# practice_2022.net
KiCad netlist of a schematic drawn in EAGLE
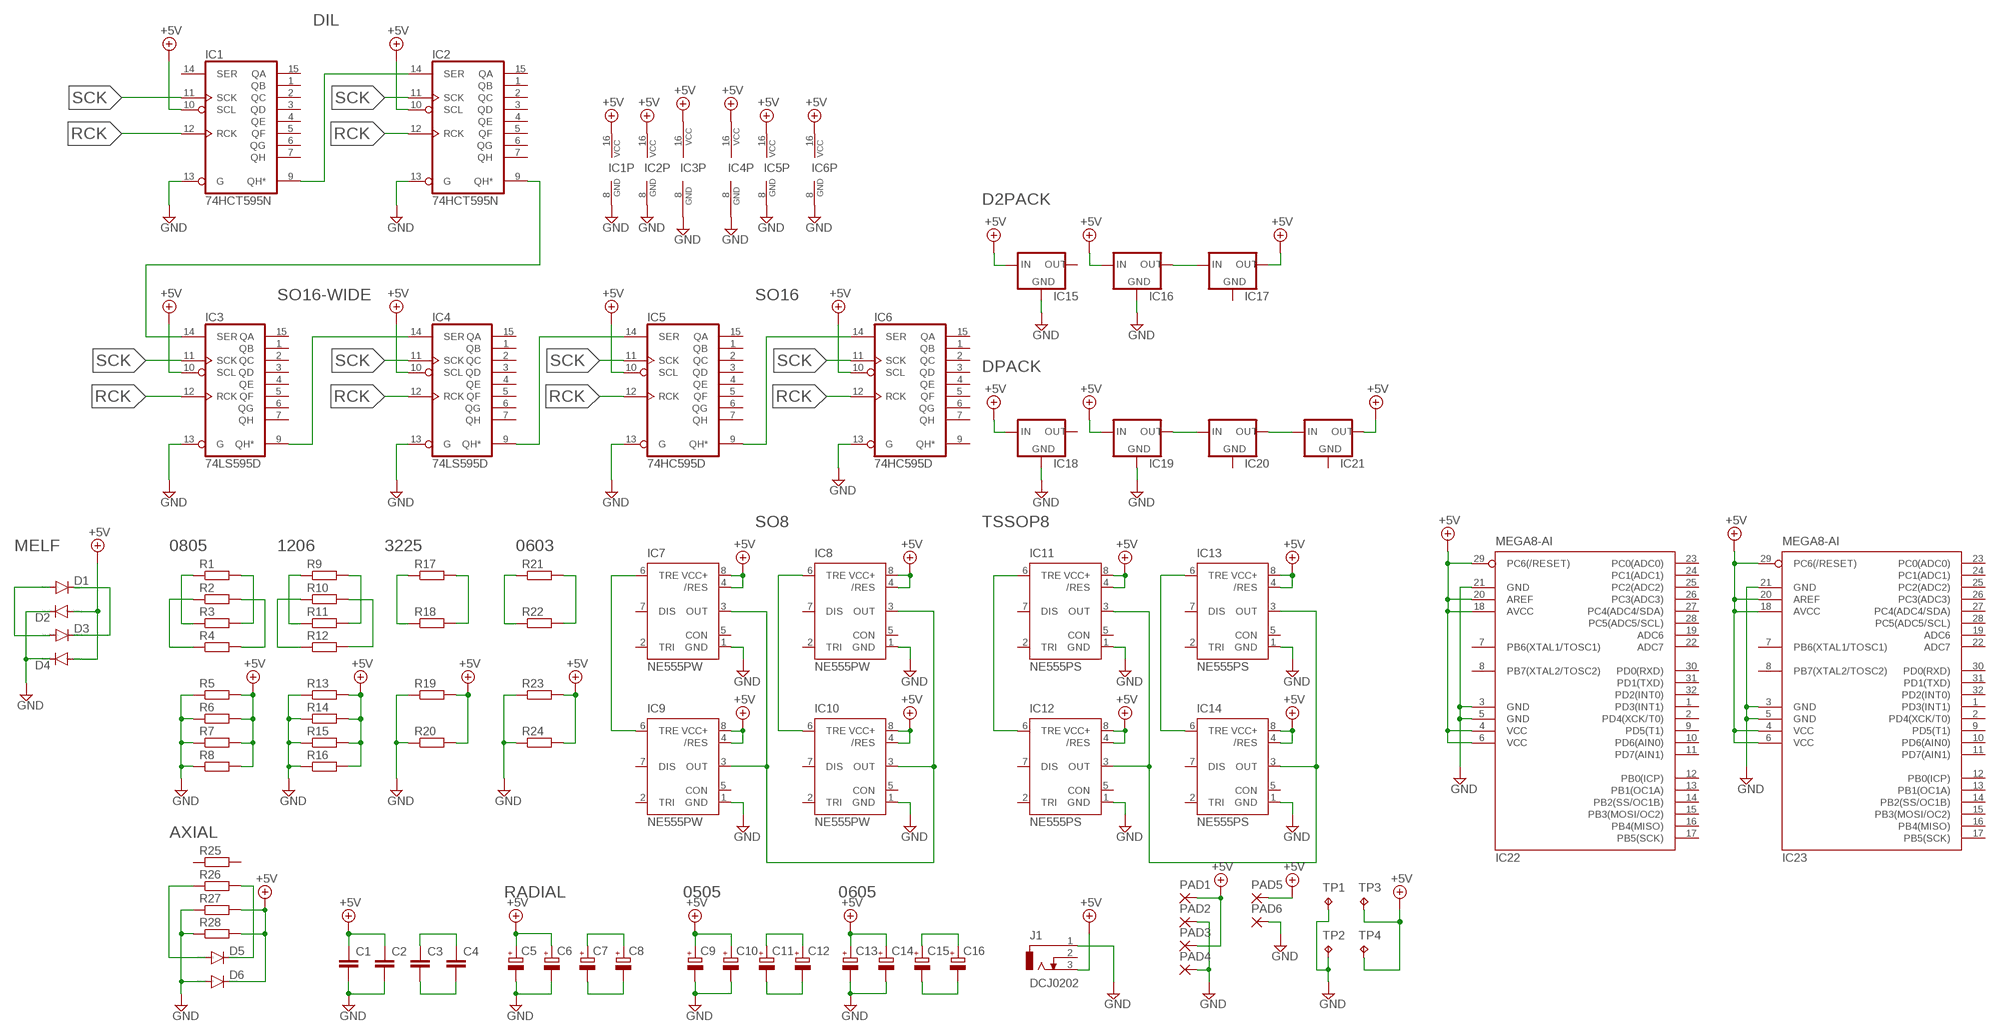
[diagram p0: schematic, sheet 1]

(export (version "E")
  (design (tool "Eeschema 10.0.6"))
  (components
    (comp (ref "C1")
      (value "C-EU050-024X044")
      (footprint "eagle-import:C050-024X044")
      (libsource (lib "eagle-import") (part "C-EU050-024X044"))
    )
    (comp (ref "C2")
      (value "C-EU050-024X044")
      (footprint "eagle-import:C050-024X044")
      (libsource (lib "eagle-import") (part "C-EU050-024X044"))
    )
    (comp (ref "C3")
      (value "C-EU050-024X044")
      (footprint "eagle-import:C050-024X044")
      (libsource (lib "eagle-import") (part "C-EU050-024X044"))
    )
    (comp (ref "C4")
      (value "C-EU050-024X044")
      (footprint "eagle-import:C050-024X044")
      (libsource (lib "eagle-import") (part "C-EU050-024X044"))
    )
    (comp (ref "C5")
      (value "CPOL-EUE5-4")
      (footprint "eagle-import:E5-4")
      (libsource (lib "eagle-import") (part "CPOL-EUE5-4"))
    )
    (comp (ref "C6")
      (value "CPOL-EUE5-4")
      (footprint "eagle-import:E5-4")
      (libsource (lib "eagle-import") (part "CPOL-EUE5-4"))
    )
    (comp (ref "C7")
      (value "CPOL-EUE2,5-6E")
      (footprint "eagle-import:E2,5-6E")
      (libsource (lib "eagle-import") (part "CPOL-EUE2,5-6E"))
    )
    (comp (ref "C8")
      (value "CPOL-EUE2,5-6E")
      (footprint "eagle-import:E2,5-6E")
      (libsource (lib "eagle-import") (part "CPOL-EUE2,5-6E"))
    )
    (comp (ref "C9")
      (value "CPOL-EU153CLV-0505")
      (footprint "eagle-import:153CLV-0505")
      (libsource (lib "eagle-import") (part "CPOL-EU153CLV-0505"))
    )
    (comp (ref "C10")
      (value "CPOL-EU153CLV-0505")
      (footprint "eagle-import:153CLV-0505")
      (libsource (lib "eagle-import") (part "CPOL-EU153CLV-0505"))
    )
    (comp (ref "C11")
      (value "CPOL-EU153CLV-0505")
      (footprint "eagle-import:153CLV-0505")
      (libsource (lib "eagle-import") (part "CPOL-EU153CLV-0505"))
    )
    (comp (ref "C12")
      (value "CPOL-EU153CLV-0505")
      (footprint "eagle-import:153CLV-0505")
      (libsource (lib "eagle-import") (part "CPOL-EU153CLV-0505"))
    )
    (comp (ref "C13")
      (value "CPOL-EU153CLV-0605")
      (footprint "eagle-import:153CLV-0605")
      (libsource (lib "eagle-import") (part "CPOL-EU153CLV-0605"))
    )
    (comp (ref "C14")
      (value "CPOL-EU153CLV-0605")
      (footprint "eagle-import:153CLV-0605")
      (libsource (lib "eagle-import") (part "CPOL-EU153CLV-0605"))
    )
    (comp (ref "C15")
      (value "CPOL-EU153CLV-0605")
      (footprint "eagle-import:153CLV-0605")
      (libsource (lib "eagle-import") (part "CPOL-EU153CLV-0605"))
    )
    (comp (ref "C16")
      (value "CPOL-EU153CLV-0605")
      (footprint "eagle-import:153CLV-0605")
      (libsource (lib "eagle-import") (part "CPOL-EU153CLV-0605"))
    )
    (comp (ref "D1")
      (value "DIODE-MINIMELF")
      (footprint "eagle-import:MINIMELF")
      (libsource (lib "eagle-import") (part "DIODE-MINIMELF"))
    )
    (comp (ref "D2")
      (value "DIODE-MINIMELF")
      (footprint "eagle-import:MINIMELF")
      (libsource (lib "eagle-import") (part "DIODE-MINIMELF"))
    )
    (comp (ref "D3")
      (value "DIODE-MINIMELF")
      (footprint "eagle-import:MINIMELF")
      (libsource (lib "eagle-import") (part "DIODE-MINIMELF"))
    )
    (comp (ref "D4")
      (value "DIODE-MINIMELF")
      (footprint "eagle-import:MINIMELF")
      (libsource (lib "eagle-import") (part "DIODE-MINIMELF"))
    )
    (comp (ref "D5")
      (value "DIODE-DO35-10")
      (footprint "eagle-import:DO35-10")
      (libsource (lib "eagle-import") (part "DIODE-DO35-10"))
    )
    (comp (ref "D6")
      (value "DIODE-DO35-10")
      (footprint "eagle-import:DO35-10")
      (libsource (lib "eagle-import") (part "DIODE-DO35-10"))
    )
    (comp (ref "IC1")
      (value "74HCT595N")
      (footprint "eagle-import:DIL16")
      (libsource (lib "eagle-import") (part "74595NHCT"))
    )
    (comp (ref "IC2")
      (value "74HCT595N")
      (footprint "eagle-import:DIL16")
      (libsource (lib "eagle-import") (part "74595NHCT"))
    )
    (comp (ref "IC3")
      (value "74LS595D")
      (footprint "eagle-import:SO16")
      (libsource (lib "eagle-import") (part "74595DLS"))
    )
    (comp (ref "IC4")
      (value "74LS595D")
      (footprint "eagle-import:SO16")
      (libsource (lib "eagle-import") (part "74595DLS"))
    )
    (comp (ref "IC5")
      (value "74HC595D")
      (footprint "eagle-import:SO16")
      (libsource (lib "eagle-import") (part "74595DHC"))
    )
    (comp (ref "IC6")
      (value "74HC595D")
      (footprint "eagle-import:SO16")
      (libsource (lib "eagle-import") (part "74595DHC"))
    )
    (comp (ref "IC7")
      (value "NE555PW")
      (footprint "eagle-import:TSSOP8")
      (libsource (lib "eagle-import") (part "NE555PW"))
    )
    (comp (ref "IC8")
      (value "NE555PW")
      (footprint "eagle-import:TSSOP8")
      (libsource (lib "eagle-import") (part "NE555PW"))
    )
    (comp (ref "IC9")
      (value "NE555PW")
      (footprint "eagle-import:TSSOP8")
      (libsource (lib "eagle-import") (part "NE555PW"))
    )
    (comp (ref "IC10")
      (value "NE555PW")
      (footprint "eagle-import:TSSOP8")
      (libsource (lib "eagle-import") (part "NE555PW"))
    )
    (comp (ref "IC11")
      (value "NE555PS")
      (footprint "eagle-import:SO08")
      (libsource (lib "eagle-import") (part "NE555PS"))
    )
    (comp (ref "IC12")
      (value "NE555PS")
      (footprint "eagle-import:SO08")
      (libsource (lib "eagle-import") (part "NE555PS"))
    )
    (comp (ref "IC13")
      (value "NE555PS")
      (footprint "eagle-import:SO08")
      (libsource (lib "eagle-import") (part "NE555PS"))
    )
    (comp (ref "IC14")
      (value "NE555PS")
      (footprint "eagle-import:SO08")
      (libsource (lib "eagle-import") (part "NE555PS"))
    )
    (comp (ref "IC15")
      (value "78XX-D2PACK")
      (footprint "eagle-import:D2PACK")
      (libsource (lib "eagle-import") (part "78XX-D2PACK"))
    )
    (comp (ref "IC16")
      (value "78XX-D2PACK")
      (footprint "eagle-import:D2PACK")
      (libsource (lib "eagle-import") (part "78XX-D2PACK"))
    )
    (comp (ref "IC17")
      (value "78XX-D2PACK")
      (footprint "eagle-import:D2PACK")
      (libsource (lib "eagle-import") (part "78XX-D2PACK"))
    )
    (comp (ref "IC18")
      (value "78XX-DPACK")
      (footprint "eagle-import:DPACK")
      (libsource (lib "eagle-import") (part "78XX-DPACK"))
    )
    (comp (ref "IC19")
      (value "78XX-DPACK")
      (footprint "eagle-import:DPACK")
      (libsource (lib "eagle-import") (part "78XX-DPACK"))
    )
    (comp (ref "IC20")
      (value "78XX-DPACK")
      (footprint "eagle-import:DPACK")
      (libsource (lib "eagle-import") (part "78XX-DPACK"))
    )
    (comp (ref "IC21")
      (value "78XX-DPACK")
      (footprint "eagle-import:DPACK")
      (libsource (lib "eagle-import") (part "78XX-DPACK"))
    )
    (comp (ref "IC22")
      (value "MEGA8-AI")
      (footprint "eagle-import:TQFP32-08")
      (fields (field (name "MPN") "ATMEGA8-16AU"))
      (libsource (lib "eagle-import") (part "MEGA8-AI"))
    )
    (comp (ref "IC23")
      (value "MEGA8-AI")
      (footprint "eagle-import:TQFP32-08")
      (fields (field (name "MPN") "ATMEGA8-16AU"))
      (libsource (lib "eagle-import") (part "MEGA8-AI"))
    )
    (comp (ref "J1")
      (value "DCJ0202")
      (footprint "eagle-import:DCJ0202")
      (libsource (lib "eagle-import") (part "DCJ0202"))
    )
    (comp (ref "PAD1")
      (value "SMD2")
      (footprint "eagle-import:SMD1,27-2,54")
      (libsource (lib "eagle-import") (part "SMD2"))
    )
    (comp (ref "PAD2")
      (value "SMD2")
      (footprint "eagle-import:SMD1,27-2,54")
      (libsource (lib "eagle-import") (part "SMD2"))
    )
    (comp (ref "PAD3")
      (value "SMD5")
      (footprint "eagle-import:SMD2,54-5,08")
      (libsource (lib "eagle-import") (part "SMD5"))
    )
    (comp (ref "PAD4")
      (value "SMD5")
      (footprint "eagle-import:SMD2,54-5,08")
      (libsource (lib "eagle-import") (part "SMD5"))
    )
    (comp (ref "PAD5")
      (value "2,54/1,0")
      (footprint "eagle-import:2,54_1,0")
      (libsource (lib "eagle-import") (part "2,54/1,0"))
    )
    (comp (ref "PAD6")
      (value "2,54/1,0")
      (footprint "eagle-import:2,54_1,0")
      (libsource (lib "eagle-import") (part "2,54/1,0"))
    )
    (comp (ref "R1")
      (value "R-EU_R0805")
      (footprint "eagle-import:R0805")
      (libsource (lib "eagle-import") (part "R-EU_R0805"))
    )
    (comp (ref "R2")
      (value "R-EU_R0805")
      (footprint "eagle-import:R0805")
      (libsource (lib "eagle-import") (part "R-EU_R0805"))
    )
    (comp (ref "R3")
      (value "R-EU_R0805")
      (footprint "eagle-import:R0805")
      (libsource (lib "eagle-import") (part "R-EU_R0805"))
    )
    (comp (ref "R4")
      (value "R-EU_R0805")
      (footprint "eagle-import:R0805")
      (libsource (lib "eagle-import") (part "R-EU_R0805"))
    )
    (comp (ref "R5")
      (value "R-EU_R0805")
      (footprint "eagle-import:R0805")
      (libsource (lib "eagle-import") (part "R-EU_R0805"))
    )
    (comp (ref "R6")
      (value "R-EU_R0805")
      (footprint "eagle-import:R0805")
      (libsource (lib "eagle-import") (part "R-EU_R0805"))
    )
    (comp (ref "R7")
      (value "R-EU_R0805")
      (footprint "eagle-import:R0805")
      (libsource (lib "eagle-import") (part "R-EU_R0805"))
    )
    (comp (ref "R8")
      (value "R-EU_R0805")
      (footprint "eagle-import:R0805")
      (libsource (lib "eagle-import") (part "R-EU_R0805"))
    )
    (comp (ref "R9")
      (value "R-EU_R1206")
      (footprint "eagle-import:R1206")
      (libsource (lib "eagle-import") (part "R-EU_R1206"))
    )
    (comp (ref "R10")
      (value "R-EU_R1206")
      (footprint "eagle-import:R1206")
      (libsource (lib "eagle-import") (part "R-EU_R1206"))
    )
    (comp (ref "R11")
      (value "R-EU_R1206")
      (footprint "eagle-import:R1206")
      (libsource (lib "eagle-import") (part "R-EU_R1206"))
    )
    (comp (ref "R12")
      (value "R-EU_R1206")
      (footprint "eagle-import:R1206")
      (libsource (lib "eagle-import") (part "R-EU_R1206"))
    )
    (comp (ref "R13")
      (value "R-EU_R1206")
      (footprint "eagle-import:R1206")
      (libsource (lib "eagle-import") (part "R-EU_R1206"))
    )
    (comp (ref "R14")
      (value "R-EU_R1206")
      (footprint "eagle-import:R1206")
      (libsource (lib "eagle-import") (part "R-EU_R1206"))
    )
    (comp (ref "R15")
      (value "R-EU_R1206")
      (footprint "eagle-import:R1206")
      (libsource (lib "eagle-import") (part "R-EU_R1206"))
    )
    (comp (ref "R16")
      (value "R-EU_R1206")
      (footprint "eagle-import:R1206")
      (libsource (lib "eagle-import") (part "R-EU_R1206"))
    )
    (comp (ref "R17")
      (value "R-EU_R3225")
      (footprint "eagle-import:R3225")
      (libsource (lib "eagle-import") (part "R-EU_R3225"))
    )
    (comp (ref "R18")
      (value "R-EU_R3225")
      (footprint "eagle-import:R3225")
      (libsource (lib "eagle-import") (part "R-EU_R3225"))
    )
    (comp (ref "R19")
      (value "R-EU_R3225")
      (footprint "eagle-import:R3225")
      (libsource (lib "eagle-import") (part "R-EU_R3225"))
    )
    (comp (ref "R20")
      (value "R-EU_R3225")
      (footprint "eagle-import:R3225")
      (libsource (lib "eagle-import") (part "R-EU_R3225"))
    )
    (comp (ref "R21")
      (value "R-EU_R0603")
      (footprint "eagle-import:R0603")
      (libsource (lib "eagle-import") (part "R-EU_R0603"))
    )
    (comp (ref "R22")
      (value "R-EU_R0603")
      (footprint "eagle-import:R0603")
      (libsource (lib "eagle-import") (part "R-EU_R0603"))
    )
    (comp (ref "R23")
      (value "R-EU_R0603")
      (footprint "eagle-import:R0603")
      (libsource (lib "eagle-import") (part "R-EU_R0603"))
    )
    (comp (ref "R24")
      (value "R-EU_R0603")
      (footprint "eagle-import:R0603")
      (libsource (lib "eagle-import") (part "R-EU_R0603"))
    )
    (comp (ref "R25")
      (value "R-EU_0207/12")
      (footprint "eagle-import:0207_12")
      (libsource (lib "eagle-import") (part "R-EU_0207/12"))
    )
    (comp (ref "R26")
      (value "R-EU_0207/12")
      (footprint "eagle-import:0207_12")
      (libsource (lib "eagle-import") (part "R-EU_0207/12"))
    )
    (comp (ref "R27")
      (value "R-EU_0207/12")
      (footprint "eagle-import:0207_12")
      (libsource (lib "eagle-import") (part "R-EU_0207/12"))
    )
    (comp (ref "R28")
      (value "R-EU_0207/12")
      (footprint "eagle-import:0207_12")
      (libsource (lib "eagle-import") (part "R-EU_0207/12"))
    )
    (comp (ref "TP1")
      (value "TPTP20SQ")
      (footprint "eagle-import:TP20SQ")
      (libsource (lib "eagle-import") (part "TPTP20SQ"))
    )
    (comp (ref "TP2")
      (value "TPTP20SQ")
      (footprint "eagle-import:TP20SQ")
      (libsource (lib "eagle-import") (part "TPTP20SQ"))
    )
    (comp (ref "TP3")
      (value "TPTP06R")
      (footprint "eagle-import:TP06R")
      (libsource (lib "eagle-import") (part "TPTP06R"))
    )
    (comp (ref "TP4")
      (value "TPTP06R")
      (footprint "eagle-import:TP06R")
      (libsource (lib "eagle-import") (part "TPTP06R"))
    )
  )
  (nets
    (net (code "1") (name "+5V") (class "Default")
      (node (ref "C1") (pin "1") (pinfunction "1_1") (pintype "passive"))
      (node (ref "C10") (pin "+") (pinfunction "+_+") (pintype "passive"))
      (node (ref "C13") (pin "+") (pinfunction "+_+") (pintype "passive"))
      (node (ref "C14") (pin "+") (pinfunction "+_+") (pintype "passive"))
      (node (ref "C2") (pin "1") (pinfunction "1_1") (pintype "passive"))
      (node (ref "C5") (pin "+") (pinfunction "+_+") (pintype "passive"))
      (node (ref "C6") (pin "+") (pinfunction "+_+") (pintype "passive"))
      (node (ref "C9") (pin "+") (pinfunction "+_+") (pintype "passive"))
      (node (ref "D2") (pin "A") (pinfunction "A_A") (pintype "passive"))
      (node (ref "D4") (pin "A") (pinfunction "A_A") (pintype "passive"))
      (node (ref "D6") (pin "C") (pinfunction "C_C") (pintype "passive"))
      (node (ref "IC1") (pin "10") (pinfunction "SCL_10") (pintype "input"))
      (node (ref "IC1") (pin "16") (pinfunction "VCC_16") (pintype "power_in"))
      (node (ref "IC10") (pin "4") (pinfunction "/RES_4") (pintype "input"))
      (node (ref "IC10") (pin "8") (pinfunction "VCC+_8") (pintype "power_in"))
      (node (ref "IC11") (pin "4") (pinfunction "/RES_4") (pintype "input"))
      (node (ref "IC11") (pin "8") (pinfunction "VCC+_8") (pintype "power_in"))
      (node (ref "IC12") (pin "4") (pinfunction "/RES_4") (pintype "input"))
      (node (ref "IC12") (pin "8") (pinfunction "VCC+_8") (pintype "power_in"))
      (node (ref "IC13") (pin "4") (pinfunction "/RES_4") (pintype "input"))
      (node (ref "IC13") (pin "8") (pinfunction "VCC+_8") (pintype "power_in"))
      (node (ref "IC14") (pin "4") (pinfunction "/RES_4") (pintype "input"))
      (node (ref "IC14") (pin "8") (pinfunction "VCC+_8") (pintype "power_in"))
      (node (ref "IC15") (pin "1") (pinfunction "IN_1") (pintype "input"))
      (node (ref "IC16") (pin "1") (pinfunction "IN_1") (pintype "input"))
      (node (ref "IC17") (pin "3") (pinfunction "OUT_3") (pintype "passive"))
      (node (ref "IC18") (pin "1") (pinfunction "IN_1") (pintype "input"))
      (node (ref "IC19") (pin "1") (pinfunction "IN_1") (pintype "input"))
      (node (ref "IC2") (pin "10") (pinfunction "SCL_10") (pintype "input"))
      (node (ref "IC2") (pin "16") (pinfunction "VCC_16") (pintype "power_in"))
      (node (ref "IC21") (pin "3") (pinfunction "OUT_3") (pintype "passive"))
      (node (ref "IC22") (pin "18") (pinfunction "AVCC_18") (pintype "power_in"))
      (node (ref "IC22") (pin "20") (pinfunction "AREF_20") (pintype "passive"))
      (node (ref "IC22") (pin "29") (pinfunction "PC6(/RESET)_29") (pintype "bidirectional"))
      (node (ref "IC22") (pin "4") (pinfunction "VCC_4") (pintype "power_in"))
      (node (ref "IC22") (pin "6") (pinfunction "VCC_6") (pintype "power_in"))
      (node (ref "IC23") (pin "18") (pinfunction "AVCC_18") (pintype "power_in"))
      (node (ref "IC23") (pin "20") (pinfunction "AREF_20") (pintype "passive"))
      (node (ref "IC23") (pin "29") (pinfunction "PC6(/RESET)_29") (pintype "bidirectional"))
      (node (ref "IC23") (pin "4") (pinfunction "VCC_4") (pintype "power_in"))
      (node (ref "IC23") (pin "6") (pinfunction "VCC_6") (pintype "power_in"))
      (node (ref "IC3") (pin "10") (pinfunction "SCL_10") (pintype "input"))
      (node (ref "IC3") (pin "16") (pinfunction "VCC_16") (pintype "power_in"))
      (node (ref "IC4") (pin "10") (pinfunction "SCL_10") (pintype "input"))
      (node (ref "IC4") (pin "16") (pinfunction "VCC_16") (pintype "power_in"))
      (node (ref "IC5") (pin "10") (pinfunction "SCL_10") (pintype "input"))
      (node (ref "IC5") (pin "16") (pinfunction "VCC_16") (pintype "power_in"))
      (node (ref "IC6") (pin "10") (pinfunction "SCL_10") (pintype "input"))
      (node (ref "IC6") (pin "16") (pinfunction "VCC_16") (pintype "power_in"))
      (node (ref "IC7") (pin "4") (pinfunction "/RES_4") (pintype "input"))
      (node (ref "IC7") (pin "8") (pinfunction "VCC+_8") (pintype "power_in"))
      (node (ref "IC8") (pin "4") (pinfunction "/RES_4") (pintype "input"))
      (node (ref "IC8") (pin "8") (pinfunction "VCC+_8") (pintype "power_in"))
      (node (ref "IC9") (pin "4") (pinfunction "/RES_4") (pintype "input"))
      (node (ref "IC9") (pin "8") (pinfunction "VCC+_8") (pintype "power_in"))
      (node (ref "J1") (pin "3") (pinfunction "3_3") (pintype "passive"))
      (node (ref "PAD1") (pin "1") (pinfunction "P_1") (pintype "passive"))
      (node (ref "PAD3") (pin "1") (pinfunction "P_1") (pintype "passive"))
      (node (ref "PAD5") (pin "1") (pinfunction "P_1") (pintype "passive"))
      (node (ref "R13") (pin "2") (pinfunction "2_2") (pintype "passive"))
      (node (ref "R14") (pin "2") (pinfunction "2_2") (pintype "passive"))
      (node (ref "R15") (pin "2") (pinfunction "2_2") (pintype "passive"))
      (node (ref "R16") (pin "2") (pinfunction "2_2") (pintype "passive"))
      (node (ref "R19") (pin "2") (pinfunction "2_2") (pintype "passive"))
      (node (ref "R20") (pin "2") (pinfunction "2_2") (pintype "passive"))
      (node (ref "R23") (pin "2") (pinfunction "2_2") (pintype "passive"))
      (node (ref "R24") (pin "2") (pinfunction "2_2") (pintype "passive"))
      (node (ref "R27") (pin "2") (pinfunction "2_2") (pintype "passive"))
      (node (ref "R28") (pin "2") (pinfunction "2_2") (pintype "passive"))
      (node (ref "R5") (pin "2") (pinfunction "2_2") (pintype "passive"))
      (node (ref "R6") (pin "2") (pinfunction "2_2") (pintype "passive"))
      (node (ref "R7") (pin "2") (pinfunction "2_2") (pintype "passive"))
      (node (ref "R8") (pin "2") (pinfunction "2_2") (pintype "passive"))
      (node (ref "TP3") (pin "TP") (pinfunction "TP_TP") (pintype "input"))
      (node (ref "TP4") (pin "TP") (pinfunction "TP_TP") (pintype "input"))
    )
    (net (code "2") (name "GND") (class "Default")
      (node (ref "C1") (pin "2") (pinfunction "2_2") (pintype "passive"))
      (node (ref "C10") (pin "-") (pinfunction "-_-") (pintype "passive"))
      (node (ref "C13") (pin "-") (pinfunction "-_-") (pintype "passive"))
      (node (ref "C14") (pin "-") (pinfunction "-_-") (pintype "passive"))
      (node (ref "C2") (pin "2") (pinfunction "2_2") (pintype "passive"))
      (node (ref "C5") (pin "-") (pinfunction "-_-") (pintype "passive"))
      (node (ref "C6") (pin "-") (pinfunction "-_-") (pintype "passive"))
      (node (ref "C9") (pin "-") (pinfunction "-_-") (pintype "passive"))
      (node (ref "D2") (pin "C") (pinfunction "C_C") (pintype "passive"))
      (node (ref "D4") (pin "C") (pinfunction "C_C") (pintype "passive"))
      (node (ref "D6") (pin "A") (pinfunction "A_A") (pintype "passive"))
      (node (ref "IC1") (pin "13") (pinfunction "G_13") (pintype "input"))
      (node (ref "IC1") (pin "8") (pinfunction "GND_8") (pintype "power_in"))
      (node (ref "IC10") (pin "1") (pinfunction "GND_1") (pintype "power_in"))
      (node (ref "IC11") (pin "1") (pinfunction "GND_1") (pintype "power_in"))
      (node (ref "IC12") (pin "1") (pinfunction "GND_1") (pintype "power_in"))
      (node (ref "IC13") (pin "1") (pinfunction "GND_1") (pintype "power_in"))
      (node (ref "IC14") (pin "1") (pinfunction "GND_1") (pintype "power_in"))
      (node (ref "IC15") (pin "2") (pinfunction "GND_2") (pintype "input"))
      (node (ref "IC16") (pin "2") (pinfunction "GND_2") (pintype "input"))
      (node (ref "IC18") (pin "4") (pinfunction "GND_4") (pintype "input"))
      (node (ref "IC19") (pin "4") (pinfunction "GND_4") (pintype "input"))
      (node (ref "IC2") (pin "13") (pinfunction "G_13") (pintype "input"))
      (node (ref "IC2") (pin "8") (pinfunction "GND_8") (pintype "power_in"))
      (node (ref "IC22") (pin "21") (pinfunction "GND_21") (pintype "power_in"))
      (node (ref "IC22") (pin "3") (pinfunction "GND_3") (pintype "power_in"))
      (node (ref "IC22") (pin "5") (pinfunction "GND_5") (pintype "power_in"))
      (node (ref "IC23") (pin "21") (pinfunction "GND_21") (pintype "power_in"))
      (node (ref "IC23") (pin "3") (pinfunction "GND_3") (pintype "power_in"))
      (node (ref "IC23") (pin "5") (pinfunction "GND_5") (pintype "power_in"))
      (node (ref "IC3") (pin "13") (pinfunction "G_13") (pintype "input"))
      (node (ref "IC3") (pin "8") (pinfunction "GND_8") (pintype "power_in"))
      (node (ref "IC4") (pin "13") (pinfunction "G_13") (pintype "input"))
      (node (ref "IC4") (pin "8") (pinfunction "GND_8") (pintype "power_in"))
      (node (ref "IC5") (pin "13") (pinfunction "G_13") (pintype "input"))
      (node (ref "IC5") (pin "8") (pinfunction "GND_8") (pintype "power_in"))
      (node (ref "IC6") (pin "13") (pinfunction "G_13") (pintype "input"))
      (node (ref "IC6") (pin "8") (pinfunction "GND_8") (pintype "power_in"))
      (node (ref "IC7") (pin "1") (pinfunction "GND_1") (pintype "power_in"))
      (node (ref "IC8") (pin "1") (pinfunction "GND_1") (pintype "power_in"))
      (node (ref "IC9") (pin "1") (pinfunction "GND_1") (pintype "power_in"))
      (node (ref "J1") (pin "1") (pinfunction "1_1") (pintype "passive"))
      (node (ref "PAD2") (pin "1") (pinfunction "P_1") (pintype "passive"))
      (node (ref "PAD4") (pin "1") (pinfunction "P_1") (pintype "passive"))
      (node (ref "PAD6") (pin "1") (pinfunction "P_1") (pintype "passive"))
      (node (ref "R13") (pin "1") (pinfunction "1_1") (pintype "passive"))
      (node (ref "R14") (pin "1") (pinfunction "1_1") (pintype "passive"))
      (node (ref "R15") (pin "1") (pinfunction "1_1") (pintype "passive"))
      (node (ref "R16") (pin "1") (pinfunction "1_1") (pintype "passive"))
      (node (ref "R19") (pin "1") (pinfunction "1_1") (pintype "passive"))
      (node (ref "R20") (pin "1") (pinfunction "1_1") (pintype "passive"))
      (node (ref "R23") (pin "1") (pinfunction "1_1") (pintype "passive"))
      (node (ref "R24") (pin "1") (pinfunction "1_1") (pintype "passive"))
      (node (ref "R27") (pin "1") (pinfunction "1_1") (pintype "passive"))
      (node (ref "R28") (pin "1") (pinfunction "1_1") (pintype "passive"))
      (node (ref "R5") (pin "1") (pinfunction "1_1") (pintype "passive"))
      (node (ref "R6") (pin "1") (pinfunction "1_1") (pintype "passive"))
      (node (ref "R7") (pin "1") (pinfunction "1_1") (pintype "passive"))
      (node (ref "R8") (pin "1") (pinfunction "1_1") (pintype "passive"))
      (node (ref "TP1") (pin "TP") (pinfunction "TP_TP") (pintype "input"))
      (node (ref "TP2") (pin "TP") (pinfunction "TP_TP") (pintype "input"))
    )
    (net (code "3") (name "Net-(C3-Pad1)") (class "Default")
      (node (ref "C3") (pin "1") (pinfunction "1_1") (pintype "passive"))
      (node (ref "C4") (pin "1") (pinfunction "1_1") (pintype "passive"))
    )
    (net (code "4") (name "Net-(C3-Pad2)") (class "Default")
      (node (ref "C3") (pin "2") (pinfunction "2_2") (pintype "passive"))
      (node (ref "C4") (pin "2") (pinfunction "2_2") (pintype "passive"))
    )
    (net (code "5") (name "Net-(C7-Pad+)") (class "Default")
      (node (ref "C7") (pin "+") (pinfunction "+_+") (pintype "passive"))
      (node (ref "C8") (pin "+") (pinfunction "+_+") (pintype "passive"))
    )
    (net (code "6") (name "Net-(C7-Pad-)") (class "Default")
      (node (ref "C7") (pin "-") (pinfunction "-_-") (pintype "passive"))
      (node (ref "C8") (pin "-") (pinfunction "-_-") (pintype "passive"))
    )
    (net (code "7") (name "Net-(C11-Pad+)") (class "Default")
      (node (ref "C11") (pin "+") (pinfunction "+_+") (pintype "passive"))
      (node (ref "C12") (pin "+") (pinfunction "+_+") (pintype "passive"))
    )
    (net (code "8") (name "Net-(C11-Pad-)") (class "Default")
      (node (ref "C11") (pin "-") (pinfunction "-_-") (pintype "passive"))
      (node (ref "C12") (pin "-") (pinfunction "-_-") (pintype "passive"))
    )
    (net (code "9") (name "Net-(C15-Pad+)") (class "Default")
      (node (ref "C15") (pin "+") (pinfunction "+_+") (pintype "passive"))
      (node (ref "C16") (pin "+") (pinfunction "+_+") (pintype "passive"))
    )
    (net (code "10") (name "Net-(C15-Pad-)") (class "Default")
      (node (ref "C15") (pin "-") (pinfunction "-_-") (pintype "passive"))
      (node (ref "C16") (pin "-") (pinfunction "-_-") (pintype "passive"))
    )
    (net (code "11") (name "Net-(D1-PadA)") (class "Default")
      (node (ref "D1") (pin "A") (pinfunction "A_A") (pintype "passive"))
      (node (ref "D3") (pin "A") (pinfunction "A_A") (pintype "passive"))
    )
    (net (code "12") (name "Net-(D1-PadC)") (class "Default")
      (node (ref "D1") (pin "C") (pinfunction "C_C") (pintype "passive"))
      (node (ref "D3") (pin "C") (pinfunction "C_C") (pintype "passive"))
    )
    (net (code "13") (name "Net-(D5-PadA)") (class "Default")
      (node (ref "D5") (pin "A") (pinfunction "A_A") (pintype "passive"))
      (node (ref "R26") (pin "1") (pinfunction "1_1") (pintype "passive"))
    )
    (net (code "14") (name "Net-(D5-PadC)") (class "Default")
      (node (ref "D5") (pin "C") (pinfunction "C_C") (pintype "passive"))
      (node (ref "R26") (pin "2") (pinfunction "2_2") (pintype "passive"))
    )
    (net (code "15") (name "Net-(IC1A-QH*)") (class "Default")
      (node (ref "IC1") (pin "9") (pinfunction "QH*_9") (pintype "tri_state"))
      (node (ref "IC2") (pin "14") (pinfunction "SER_14") (pintype "input"))
    )
    (net (code "16") (name "Net-(IC2A-QH*)") (class "Default")
      (node (ref "IC2") (pin "9") (pinfunction "QH*_9") (pintype "tri_state"))
      (node (ref "IC3") (pin "14") (pinfunction "SER_14") (pintype "input"))
    )
    (net (code "17") (name "Net-(IC3A-QH*)") (class "Default")
      (node (ref "IC3") (pin "9") (pinfunction "QH*_9") (pintype "tri_state"))
      (node (ref "IC4") (pin "14") (pinfunction "SER_14") (pintype "input"))
    )
    (net (code "18") (name "Net-(IC4A-QH*)") (class "Default")
      (node (ref "IC4") (pin "9") (pinfunction "QH*_9") (pintype "tri_state"))
      (node (ref "IC5") (pin "14") (pinfunction "SER_14") (pintype "input"))
    )
    (net (code "19") (name "Net-(IC5A-QH*)") (class "Default")
      (node (ref "IC5") (pin "9") (pinfunction "QH*_9") (pintype "tri_state"))
      (node (ref "IC6") (pin "14") (pinfunction "SER_14") (pintype "input"))
    )
    (net (code "20") (name "Net-(IC7-TRE)") (class "Default")
      (node (ref "IC7") (pin "6") (pinfunction "TRE_6") (pintype "input"))
      (node (ref "IC9") (pin "6") (pinfunction "TRE_6") (pintype "input"))
    )
    (net (code "21") (name "Net-(IC10-OUT)") (class "Default")
      (node (ref "IC10") (pin "3") (pinfunction "OUT_3") (pintype "output"))
      (node (ref "IC7") (pin "3") (pinfunction "OUT_3") (pintype "output"))
      (node (ref "IC8") (pin "3") (pinfunction "OUT_3") (pintype "output"))
      (node (ref "IC9") (pin "3") (pinfunction "OUT_3") (pintype "output"))
    )
    (net (code "22") (name "Net-(IC10-TRE)") (class "Default")
      (node (ref "IC10") (pin "6") (pinfunction "TRE_6") (pintype "input"))
      (node (ref "IC8") (pin "6") (pinfunction "TRE_6") (pintype "input"))
    )
    (net (code "23") (name "Net-(IC11-OUT)") (class "Default")
      (node (ref "IC11") (pin "3") (pinfunction "OUT_3") (pintype "output"))
      (node (ref "IC12") (pin "3") (pinfunction "OUT_3") (pintype "output"))
      (node (ref "IC13") (pin "3") (pinfunction "OUT_3") (pintype "output"))
      (node (ref "IC14") (pin "3") (pinfunction "OUT_3") (pintype "output"))
    )
    (net (code "24") (name "Net-(IC11-TRE)") (class "Default")
      (node (ref "IC11") (pin "6") (pinfunction "TRE_6") (pintype "input"))
      (node (ref "IC12") (pin "6") (pinfunction "TRE_6") (pintype "input"))
    )
    (net (code "25") (name "Net-(IC13-TRE)") (class "Default")
      (node (ref "IC13") (pin "6") (pinfunction "TRE_6") (pintype "input"))
      (node (ref "IC14") (pin "6") (pinfunction "TRE_6") (pintype "input"))
    )
    (net (code "26") (name "Net-(IC16-OUT)") (class "Default")
      (node (ref "IC16") (pin "3") (pinfunction "OUT_3") (pintype "passive"))
      (node (ref "IC17") (pin "1") (pinfunction "IN_1") (pintype "input"))
    )
    (net (code "27") (name "Net-(IC19-OUT)") (class "Default")
      (node (ref "IC19") (pin "3") (pinfunction "OUT_3") (pintype "passive"))
      (node (ref "IC20") (pin "1") (pinfunction "IN_1") (pintype "input"))
    )
    (net (code "28") (name "Net-(IC20-OUT)") (class "Default")
      (node (ref "IC20") (pin "3") (pinfunction "OUT_3") (pintype "passive"))
      (node (ref "IC21") (pin "1") (pinfunction "IN_1") (pintype "input"))
    )
    (net (code "29") (name "Net-(R1-Pad1)") (class "Default")
      (node (ref "R1") (pin "1") (pinfunction "1_1") (pintype "passive"))
      (node (ref "R3") (pin "1") (pinfunction "1_1") (pintype "passive"))
    )
    (net (code "30") (name "Net-(R1-Pad2)") (class "Default")
      (node (ref "R1") (pin "2") (pinfunction "2_2") (pintype "passive"))
      (node (ref "R3") (pin "2") (pinfunction "2_2") (pintype "passive"))
    )
    (net (code "31") (name "Net-(R2-Pad1)") (class "Default")
      (node (ref "R2") (pin "1") (pinfunction "1_1") (pintype "passive"))
      (node (ref "R4") (pin "1") (pinfunction "1_1") (pintype "passive"))
    )
    (net (code "32") (name "Net-(R2-Pad2)") (class "Default")
      (node (ref "R2") (pin "2") (pinfunction "2_2") (pintype "passive"))
      (node (ref "R4") (pin "2") (pinfunction "2_2") (pintype "passive"))
    )
    (net (code "33") (name "Net-(R10-Pad1)") (class "Default")
      (node (ref "R10") (pin "1") (pinfunction "1_1") (pintype "passive"))
      (node (ref "R12") (pin "1") (pinfunction "1_1") (pintype "passive"))
    )
    (net (code "34") (name "Net-(R10-Pad2)") (class "Default")
      (node (ref "R10") (pin "2") (pinfunction "2_2") (pintype "passive"))
      (node (ref "R12") (pin "2") (pinfunction "2_2") (pintype "passive"))
    )
    (net (code "35") (name "Net-(R11-Pad1)") (class "Default")
      (node (ref "R11") (pin "1") (pinfunction "1_1") (pintype "passive"))
      (node (ref "R9") (pin "1") (pinfunction "1_1") (pintype "passive"))
    )
    (net (code "36") (name "Net-(R11-Pad2)") (class "Default")
      (node (ref "R11") (pin "2") (pinfunction "2_2") (pintype "passive"))
      (node (ref "R9") (pin "2") (pinfunction "2_2") (pintype "passive"))
    )
    (net (code "37") (name "Net-(R17-Pad1)") (class "Default")
      (node (ref "R17") (pin "1") (pinfunction "1_1") (pintype "passive"))
      (node (ref "R18") (pin "1") (pinfunction "1_1") (pintype "passive"))
    )
    (net (code "38") (name "Net-(R17-Pad2)") (class "Default")
      (node (ref "R17") (pin "2") (pinfunction "2_2") (pintype "passive"))
      (node (ref "R18") (pin "2") (pinfunction "2_2") (pintype "passive"))
    )
    (net (code "39") (name "Net-(R21-Pad1)") (class "Default")
      (node (ref "R21") (pin "1") (pinfunction "1_1") (pintype "passive"))
      (node (ref "R22") (pin "1") (pinfunction "1_1") (pintype "passive"))
    )
    (net (code "40") (name "Net-(R21-Pad2)") (class "Default")
      (node (ref "R21") (pin "2") (pinfunction "2_2") (pintype "passive"))
      (node (ref "R22") (pin "2") (pinfunction "2_2") (pintype "passive"))
    )
    (net (code "41") (name "RCK") (class "Default")
      (node (ref "IC1") (pin "12") (pinfunction "RCK_12") (pintype "input"))
      (node (ref "IC2") (pin "12") (pinfunction "RCK_12") (pintype "input"))
      (node (ref "IC3") (pin "12") (pinfunction "RCK_12") (pintype "input"))
      (node (ref "IC4") (pin "12") (pinfunction "RCK_12") (pintype "input"))
      (node (ref "IC5") (pin "12") (pinfunction "RCK_12") (pintype "input"))
      (node (ref "IC6") (pin "12") (pinfunction "RCK_12") (pintype "input"))
    )
    (net (code "42") (name "SCK") (class "Default")
      (node (ref "IC1") (pin "11") (pinfunction "SCK_11") (pintype "input"))
      (node (ref "IC2") (pin "11") (pinfunction "SCK_11") (pintype "input"))
      (node (ref "IC3") (pin "11") (pinfunction "SCK_11") (pintype "input"))
      (node (ref "IC4") (pin "11") (pinfunction "SCK_11") (pintype "input"))
      (node (ref "IC5") (pin "11") (pinfunction "SCK_11") (pintype "input"))
      (node (ref "IC6") (pin "11") (pinfunction "SCK_11") (pintype "input"))
    )
    (net (code "43") (name "unconnected-(IC1A-QA-Pad15)") (class "Default")
      (node (ref "IC1") (pin "15") (pinfunction "QA_15") (pintype "tri_state"))
    )
    (net (code "44") (name "unconnected-(IC1A-QB-Pad1)") (class "Default")
      (node (ref "IC1") (pin "1") (pinfunction "QB_1") (pintype "tri_state"))
    )
    (net (code "45") (name "unconnected-(IC1A-QC-Pad2)") (class "Default")
      (node (ref "IC1") (pin "2") (pinfunction "QC_2") (pintype "tri_state"))
    )
    (net (code "46") (name "unconnected-(IC1A-QD-Pad3)") (class "Default")
      (node (ref "IC1") (pin "3") (pinfunction "QD_3") (pintype "tri_state"))
    )
    (net (code "47") (name "unconnected-(IC1A-QE-Pad4)") (class "Default")
      (node (ref "IC1") (pin "4") (pinfunction "QE_4") (pintype "tri_state"))
    )
    (net (code "48") (name "unconnected-(IC1A-QF-Pad5)") (class "Default")
      (node (ref "IC1") (pin "5") (pinfunction "QF_5") (pintype "tri_state"))
    )
    (net (code "49") (name "unconnected-(IC1A-QG-Pad6)") (class "Default")
      (node (ref "IC1") (pin "6") (pinfunction "QG_6") (pintype "tri_state"))
    )
    (net (code "50") (name "unconnected-(IC1A-QH-Pad7)") (class "Default")
      (node (ref "IC1") (pin "7") (pinfunction "QH_7") (pintype "tri_state"))
    )
    (net (code "51") (name "unconnected-(IC1A-SER-Pad14)") (class "Default")
      (node (ref "IC1") (pin "14") (pinfunction "SER_14") (pintype "input"))
    )
    (net (code "52") (name "unconnected-(IC2A-QA-Pad15)") (class "Default")
      (node (ref "IC2") (pin "15") (pinfunction "QA_15") (pintype "tri_state"))
    )
    (net (code "53") (name "unconnected-(IC2A-QB-Pad1)") (class "Default")
      (node (ref "IC2") (pin "1") (pinfunction "QB_1") (pintype "tri_state"))
    )
    (net (code "54") (name "unconnected-(IC2A-QC-Pad2)") (class "Default")
      (node (ref "IC2") (pin "2") (pinfunction "QC_2") (pintype "tri_state"))
    )
    (net (code "55") (name "unconnected-(IC2A-QD-Pad3)") (class "Default")
      (node (ref "IC2") (pin "3") (pinfunction "QD_3") (pintype "tri_state"))
    )
    (net (code "56") (name "unconnected-(IC2A-QE-Pad4)") (class "Default")
      (node (ref "IC2") (pin "4") (pinfunction "QE_4") (pintype "tri_state"))
    )
    (net (code "57") (name "unconnected-(IC2A-QF-Pad5)") (class "Default")
      (node (ref "IC2") (pin "5") (pinfunction "QF_5") (pintype "tri_state"))
    )
    (net (code "58") (name "unconnected-(IC2A-QG-Pad6)") (class "Default")
      (node (ref "IC2") (pin "6") (pinfunction "QG_6") (pintype "tri_state"))
    )
    (net (code "59") (name "unconnected-(IC2A-QH-Pad7)") (class "Default")
      (node (ref "IC2") (pin "7") (pinfunction "QH_7") (pintype "tri_state"))
    )
    (net (code "60") (name "unconnected-(IC3A-QA-Pad15)") (class "Default")
      (node (ref "IC3") (pin "15") (pinfunction "QA_15") (pintype "tri_state"))
    )
    (net (code "61") (name "unconnected-(IC3A-QB-Pad1)") (class "Default")
      (node (ref "IC3") (pin "1") (pinfunction "QB_1") (pintype "tri_state"))
    )
    (net (code "62") (name "unconnected-(IC3A-QC-Pad2)") (class "Default")
      (node (ref "IC3") (pin "2") (pinfunction "QC_2") (pintype "tri_state"))
    )
    (net (code "63") (name "unconnected-(IC3A-QD-Pad3)") (class "Default")
      (node (ref "IC3") (pin "3") (pinfunction "QD_3") (pintype "tri_state"))
    )
    (net (code "64") (name "unconnected-(IC3A-QE-Pad4)") (class "Default")
      (node (ref "IC3") (pin "4") (pinfunction "QE_4") (pintype "tri_state"))
    )
    (net (code "65") (name "unconnected-(IC3A-QF-Pad5)") (class "Default")
      (node (ref "IC3") (pin "5") (pinfunction "QF_5") (pintype "tri_state"))
    )
    (net (code "66") (name "unconnected-(IC3A-QG-Pad6)") (class "Default")
      (node (ref "IC3") (pin "6") (pinfunction "QG_6") (pintype "tri_state"))
    )
    (net (code "67") (name "unconnected-(IC3A-QH-Pad7)") (class "Default")
      (node (ref "IC3") (pin "7") (pinfunction "QH_7") (pintype "tri_state"))
    )
    (net (code "68") (name "unconnected-(IC4A-QA-Pad15)") (class "Default")
      (node (ref "IC4") (pin "15") (pinfunction "QA_15") (pintype "tri_state"))
    )
    (net (code "69") (name "unconnected-(IC4A-QB-Pad1)") (class "Default")
      (node (ref "IC4") (pin "1") (pinfunction "QB_1") (pintype "tri_state"))
    )
    (net (code "70") (name "unconnected-(IC4A-QC-Pad2)") (class "Default")
      (node (ref "IC4") (pin "2") (pinfunction "QC_2") (pintype "tri_state"))
    )
    (net (code "71") (name "unconnected-(IC4A-QD-Pad3)") (class "Default")
      (node (ref "IC4") (pin "3") (pinfunction "QD_3") (pintype "tri_state"))
    )
    (net (code "72") (name "unconnected-(IC4A-QE-Pad4)") (class "Default")
      (node (ref "IC4") (pin "4") (pinfunction "QE_4") (pintype "tri_state"))
    )
    (net (code "73") (name "unconnected-(IC4A-QF-Pad5)") (class "Default")
      (node (ref "IC4") (pin "5") (pinfunction "QF_5") (pintype "tri_state"))
    )
    (net (code "74") (name "unconnected-(IC4A-QG-Pad6)") (class "Default")
      (node (ref "IC4") (pin "6") (pinfunction "QG_6") (pintype "tri_state"))
    )
    (net (code "75") (name "unconnected-(IC4A-QH-Pad7)") (class "Default")
      (node (ref "IC4") (pin "7") (pinfunction "QH_7") (pintype "tri_state"))
    )
    (net (code "76") (name "unconnected-(IC5A-QA-Pad15)") (class "Default")
      (node (ref "IC5") (pin "15") (pinfunction "QA_15") (pintype "tri_state"))
    )
    (net (code "77") (name "unconnected-(IC5A-QB-Pad1)") (class "Default")
      (node (ref "IC5") (pin "1") (pinfunction "QB_1") (pintype "tri_state"))
    )
    (net (code "78") (name "unconnected-(IC5A-QC-Pad2)") (class "Default")
      (node (ref "IC5") (pin "2") (pinfunction "QC_2") (pintype "tri_state"))
    )
    (net (code "79") (name "unconnected-(IC5A-QD-Pad3)") (class "Default")
      (node (ref "IC5") (pin "3") (pinfunction "QD_3") (pintype "tri_state"))
    )
    (net (code "80") (name "unconnected-(IC5A-QE-Pad4)") (class "Default")
      (node (ref "IC5") (pin "4") (pinfunction "QE_4") (pintype "tri_state"))
    )
    (net (code "81") (name "unconnected-(IC5A-QF-Pad5)") (class "Default")
      (node (ref "IC5") (pin "5") (pinfunction "QF_5") (pintype "tri_state"))
    )
    (net (code "82") (name "unconnected-(IC5A-QG-Pad6)") (class "Default")
      (node (ref "IC5") (pin "6") (pinfunction "QG_6") (pintype "tri_state"))
    )
    (net (code "83") (name "unconnected-(IC5A-QH-Pad7)") (class "Default")
      (node (ref "IC5") (pin "7") (pinfunction "QH_7") (pintype "tri_state"))
    )
    (net (code "84") (name "unconnected-(IC6A-QA-Pad15)") (class "Default")
      (node (ref "IC6") (pin "15") (pinfunction "QA_15") (pintype "tri_state"))
    )
    (net (code "85") (name "unconnected-(IC6A-QB-Pad1)") (class "Default")
      (node (ref "IC6") (pin "1") (pinfunction "QB_1") (pintype "tri_state"))
    )
    (net (code "86") (name "unconnected-(IC6A-QC-Pad2)") (class "Default")
      (node (ref "IC6") (pin "2") (pinfunction "QC_2") (pintype "tri_state"))
    )
    (net (code "87") (name "unconnected-(IC6A-QD-Pad3)") (class "Default")
      (node (ref "IC6") (pin "3") (pinfunction "QD_3") (pintype "tri_state"))
    )
    (net (code "88") (name "unconnected-(IC6A-QE-Pad4)") (class "Default")
      (node (ref "IC6") (pin "4") (pinfunction "QE_4") (pintype "tri_state"))
    )
    (net (code "89") (name "unconnected-(IC6A-QF-Pad5)") (class "Default")
      (node (ref "IC6") (pin "5") (pinfunction "QF_5") (pintype "tri_state"))
    )
    (net (code "90") (name "unconnected-(IC6A-QG-Pad6)") (class "Default")
      (node (ref "IC6") (pin "6") (pinfunction "QG_6") (pintype "tri_state"))
    )
    (net (code "91") (name "unconnected-(IC6A-QH*-Pad9)") (class "Default")
      (node (ref "IC6") (pin "9") (pinfunction "QH*_9") (pintype "tri_state"))
    )
    (net (code "92") (name "unconnected-(IC6A-QH-Pad7)") (class "Default")
      (node (ref "IC6") (pin "7") (pinfunction "QH_7") (pintype "tri_state"))
    )
    (net (code "93") (name "unconnected-(IC7-CON-Pad5)") (class "Default")
      (node (ref "IC7") (pin "5") (pinfunction "CON_5") (pintype "input"))
    )
    (net (code "94") (name "unconnected-(IC7-DIS-Pad7)") (class "Default")
      (node (ref "IC7") (pin "7") (pinfunction "DIS_7") (pintype "input"))
    )
    (net (code "95") (name "unconnected-(IC7-TRI-Pad2)") (class "Default")
      (node (ref "IC7") (pin "2") (pinfunction "TRI_2") (pintype "input"))
    )
    (net (code "96") (name "unconnected-(IC8-CON-Pad5)") (class "Default")
      (node (ref "IC8") (pin "5") (pinfunction "CON_5") (pintype "input"))
    )
    (net (code "97") (name "unconnected-(IC8-DIS-Pad7)") (class "Default")
      (node (ref "IC8") (pin "7") (pinfunction "DIS_7") (pintype "input"))
    )
    (net (code "98") (name "unconnected-(IC8-TRI-Pad2)") (class "Default")
      (node (ref "IC8") (pin "2") (pinfunction "TRI_2") (pintype "input"))
    )
    (net (code "99") (name "unconnected-(IC9-CON-Pad5)") (class "Default")
      (node (ref "IC9") (pin "5") (pinfunction "CON_5") (pintype "input"))
    )
    (net (code "100") (name "unconnected-(IC9-DIS-Pad7)") (class "Default")
      (node (ref "IC9") (pin "7") (pinfunction "DIS_7") (pintype "input"))
    )
    (net (code "101") (name "unconnected-(IC9-TRI-Pad2)") (class "Default")
      (node (ref "IC9") (pin "2") (pinfunction "TRI_2") (pintype "input"))
    )
    (net (code "102") (name "unconnected-(IC10-CON-Pad5)") (class "Default")
      (node (ref "IC10") (pin "5") (pinfunction "CON_5") (pintype "input"))
    )
    (net (code "103") (name "unconnected-(IC10-DIS-Pad7)") (class "Default")
      (node (ref "IC10") (pin "7") (pinfunction "DIS_7") (pintype "input"))
    )
    (net (code "104") (name "unconnected-(IC10-TRI-Pad2)") (class "Default")
      (node (ref "IC10") (pin "2") (pinfunction "TRI_2") (pintype "input"))
    )
    (net (code "105") (name "unconnected-(IC11-CON-Pad5)") (class "Default")
      (node (ref "IC11") (pin "5") (pinfunction "CON_5") (pintype "input"))
    )
    (net (code "106") (name "unconnected-(IC11-DIS-Pad7)") (class "Default")
      (node (ref "IC11") (pin "7") (pinfunction "DIS_7") (pintype "input"))
    )
    (net (code "107") (name "unconnected-(IC11-TRI-Pad2)") (class "Default")
      (node (ref "IC11") (pin "2") (pinfunction "TRI_2") (pintype "input"))
    )
    (net (code "108") (name "unconnected-(IC12-CON-Pad5)") (class "Default")
      (node (ref "IC12") (pin "5") (pinfunction "CON_5") (pintype "input"))
    )
    (net (code "109") (name "unconnected-(IC12-DIS-Pad7)") (class "Default")
      (node (ref "IC12") (pin "7") (pinfunction "DIS_7") (pintype "input"))
    )
    (net (code "110") (name "unconnected-(IC12-TRI-Pad2)") (class "Default")
      (node (ref "IC12") (pin "2") (pinfunction "TRI_2") (pintype "input"))
    )
    (net (code "111") (name "unconnected-(IC13-CON-Pad5)") (class "Default")
      (node (ref "IC13") (pin "5") (pinfunction "CON_5") (pintype "input"))
    )
    (net (code "112") (name "unconnected-(IC13-DIS-Pad7)") (class "Default")
      (node (ref "IC13") (pin "7") (pinfunction "DIS_7") (pintype "input"))
    )
    (net (code "113") (name "unconnected-(IC13-TRI-Pad2)") (class "Default")
      (node (ref "IC13") (pin "2") (pinfunction "TRI_2") (pintype "input"))
    )
    (net (code "114") (name "unconnected-(IC14-CON-Pad5)") (class "Default")
      (node (ref "IC14") (pin "5") (pinfunction "CON_5") (pintype "input"))
    )
    (net (code "115") (name "unconnected-(IC14-DIS-Pad7)") (class "Default")
      (node (ref "IC14") (pin "7") (pinfunction "DIS_7") (pintype "input"))
    )
    (net (code "116") (name "unconnected-(IC14-TRI-Pad2)") (class "Default")
      (node (ref "IC14") (pin "2") (pinfunction "TRI_2") (pintype "input"))
    )
    (net (code "117") (name "unconnected-(IC15-OUT-Pad3)") (class "Default")
      (node (ref "IC15") (pin "3") (pinfunction "OUT_3") (pintype "passive"))
    )
    (net (code "118") (name "unconnected-(IC17-GND-Pad2)") (class "Default")
      (node (ref "IC17") (pin "2") (pinfunction "GND_2") (pintype "input"))
    )
    (net (code "119") (name "unconnected-(IC18-OUT-Pad3)") (class "Default")
      (node (ref "IC18") (pin "3") (pinfunction "OUT_3") (pintype "passive"))
    )
    (net (code "120") (name "unconnected-(IC20-GND-Pad4)") (class "Default")
      (node (ref "IC20") (pin "4") (pinfunction "GND_4") (pintype "input"))
    )
    (net (code "121") (name "unconnected-(IC21-GND-Pad4)") (class "Default")
      (node (ref "IC21") (pin "4") (pinfunction "GND_4") (pintype "input"))
    )
    (net (code "122") (name "unconnected-(IC22-ADC6-Pad19)") (class "Default")
      (node (ref "IC22") (pin "19") (pinfunction "ADC6_19") (pintype "bidirectional"))
    )
    (net (code "123") (name "unconnected-(IC22-ADC7-Pad22)") (class "Default")
      (node (ref "IC22") (pin "22") (pinfunction "ADC7_22") (pintype "bidirectional"))
    )
    (net (code "124") (name "unconnected-(IC22-PB0(ICP)-Pad12)") (class "Default")
      (node (ref "IC22") (pin "12") (pinfunction "PB0(ICP)_12") (pintype "bidirectional"))
    )
    (net (code "125") (name "unconnected-(IC22-PB1(OC1A)-Pad13)") (class "Default")
      (node (ref "IC22") (pin "13") (pinfunction "PB1(OC1A)_13") (pintype "bidirectional"))
    )
    (net (code "126") (name "unconnected-(IC22-PB2(SS{slash}OC1B)-Pad14)") (class "Default")
      (node (ref "IC22") (pin "14") (pinfunction "PB2(SS/OC1B)_14") (pintype "bidirectional"))
    )
    (net (code "127") (name "unconnected-(IC22-PB3(MOSI{slash}OC2)-Pad15)") (class "Default")
      (node (ref "IC22") (pin "15") (pinfunction "PB3(MOSI/OC2)_15") (pintype "bidirectional"))
    )
    (net (code "128") (name "unconnected-(IC22-PB4(MISO)-Pad16)") (class "Default")
      (node (ref "IC22") (pin "16") (pinfunction "PB4(MISO)_16") (pintype "bidirectional"))
    )
    (net (code "129") (name "unconnected-(IC22-PB5(SCK)-Pad17)") (class "Default")
      (node (ref "IC22") (pin "17") (pinfunction "PB5(SCK)_17") (pintype "bidirectional"))
    )
    (net (code "130") (name "unconnected-(IC22-PB6(XTAL1{slash}TOSC1)-Pad7)") (class "Default")
      (node (ref "IC22") (pin "7") (pinfunction "PB6(XTAL1/TOSC1)_7") (pintype "bidirectional"))
    )
    (net (code "131") (name "unconnected-(IC22-PB7(XTAL2{slash}TOSC2)-Pad8)") (class "Default")
      (node (ref "IC22") (pin "8") (pinfunction "PB7(XTAL2/TOSC2)_8") (pintype "bidirectional"))
    )
    (net (code "132") (name "unconnected-(IC22-PC0(ADC0)-Pad23)") (class "Default")
      (node (ref "IC22") (pin "23") (pinfunction "PC0(ADC0)_23") (pintype "bidirectional"))
    )
    (net (code "133") (name "unconnected-(IC22-PC1(ADC1)-Pad24)") (class "Default")
      (node (ref "IC22") (pin "24") (pinfunction "PC1(ADC1)_24") (pintype "bidirectional"))
    )
    (net (code "134") (name "unconnected-(IC22-PC2(ADC2)-Pad25)") (class "Default")
      (node (ref "IC22") (pin "25") (pinfunction "PC2(ADC2)_25") (pintype "bidirectional"))
    )
    (net (code "135") (name "unconnected-(IC22-PC3(ADC3)-Pad26)") (class "Default")
      (node (ref "IC22") (pin "26") (pinfunction "PC3(ADC3)_26") (pintype "bidirectional"))
    )
    (net (code "136") (name "unconnected-(IC22-PC4(ADC4{slash}SDA)-Pad27)") (class "Default")
      (node (ref "IC22") (pin "27") (pinfunction "PC4(ADC4/SDA)_27") (pintype "bidirectional"))
    )
    (net (code "137") (name "unconnected-(IC22-PC5(ADC5{slash}SCL)-Pad28)") (class "Default")
      (node (ref "IC22") (pin "28") (pinfunction "PC5(ADC5/SCL)_28") (pintype "bidirectional"))
    )
    (net (code "138") (name "unconnected-(IC22-PD0(RXD)-Pad30)") (class "Default")
      (node (ref "IC22") (pin "30") (pinfunction "PD0(RXD)_30") (pintype "bidirectional"))
    )
    (net (code "139") (name "unconnected-(IC22-PD1(TXD)-Pad31)") (class "Default")
      (node (ref "IC22") (pin "31") (pinfunction "PD1(TXD)_31") (pintype "bidirectional"))
    )
    (net (code "140") (name "unconnected-(IC22-PD2(INT0)-Pad32)") (class "Default")
      (node (ref "IC22") (pin "32") (pinfunction "PD2(INT0)_32") (pintype "bidirectional"))
    )
    (net (code "141") (name "unconnected-(IC22-PD3(INT1)-Pad1)") (class "Default")
      (node (ref "IC22") (pin "1") (pinfunction "PD3(INT1)_1") (pintype "bidirectional"))
    )
    (net (code "142") (name "unconnected-(IC22-PD4(XCK{slash}T0)-Pad2)") (class "Default")
      (node (ref "IC22") (pin "2") (pinfunction "PD4(XCK/T0)_2") (pintype "bidirectional"))
    )
    (net (code "143") (name "unconnected-(IC22-PD5(T1)-Pad9)") (class "Default")
      (node (ref "IC22") (pin "9") (pinfunction "PD5(T1)_9") (pintype "bidirectional"))
    )
    (net (code "144") (name "unconnected-(IC22-PD6(AIN0)-Pad10)") (class "Default")
      (node (ref "IC22") (pin "10") (pinfunction "PD6(AIN0)_10") (pintype "bidirectional"))
    )
    (net (code "145") (name "unconnected-(IC22-PD7(AIN1)-Pad11)") (class "Default")
      (node (ref "IC22") (pin "11") (pinfunction "PD7(AIN1)_11") (pintype "bidirectional"))
    )
    (net (code "146") (name "unconnected-(IC23-ADC6-Pad19)") (class "Default")
      (node (ref "IC23") (pin "19") (pinfunction "ADC6_19") (pintype "bidirectional"))
    )
    (net (code "147") (name "unconnected-(IC23-ADC7-Pad22)") (class "Default")
      (node (ref "IC23") (pin "22") (pinfunction "ADC7_22") (pintype "bidirectional"))
    )
    (net (code "148") (name "unconnected-(IC23-PB0(ICP)-Pad12)") (class "Default")
      (node (ref "IC23") (pin "12") (pinfunction "PB0(ICP)_12") (pintype "bidirectional"))
    )
    (net (code "149") (name "unconnected-(IC23-PB1(OC1A)-Pad13)") (class "Default")
      (node (ref "IC23") (pin "13") (pinfunction "PB1(OC1A)_13") (pintype "bidirectional"))
    )
    (net (code "150") (name "unconnected-(IC23-PB2(SS{slash}OC1B)-Pad14)") (class "Default")
      (node (ref "IC23") (pin "14") (pinfunction "PB2(SS/OC1B)_14") (pintype "bidirectional"))
    )
    (net (code "151") (name "unconnected-(IC23-PB3(MOSI{slash}OC2)-Pad15)") (class "Default")
      (node (ref "IC23") (pin "15") (pinfunction "PB3(MOSI/OC2)_15") (pintype "bidirectional"))
    )
    (net (code "152") (name "unconnected-(IC23-PB4(MISO)-Pad16)") (class "Default")
      (node (ref "IC23") (pin "16") (pinfunction "PB4(MISO)_16") (pintype "bidirectional"))
    )
    (net (code "153") (name "unconnected-(IC23-PB5(SCK)-Pad17)") (class "Default")
      (node (ref "IC23") (pin "17") (pinfunction "PB5(SCK)_17") (pintype "bidirectional"))
    )
    (net (code "154") (name "unconnected-(IC23-PB6(XTAL1{slash}TOSC1)-Pad7)") (class "Default")
      (node (ref "IC23") (pin "7") (pinfunction "PB6(XTAL1/TOSC1)_7") (pintype "bidirectional"))
    )
    (net (code "155") (name "unconnected-(IC23-PB7(XTAL2{slash}TOSC2)-Pad8)") (class "Default")
      (node (ref "IC23") (pin "8") (pinfunction "PB7(XTAL2/TOSC2)_8") (pintype "bidirectional"))
    )
    (net (code "156") (name "unconnected-(IC23-PC0(ADC0)-Pad23)") (class "Default")
      (node (ref "IC23") (pin "23") (pinfunction "PC0(ADC0)_23") (pintype "bidirectional"))
    )
    (net (code "157") (name "unconnected-(IC23-PC1(ADC1)-Pad24)") (class "Default")
      (node (ref "IC23") (pin "24") (pinfunction "PC1(ADC1)_24") (pintype "bidirectional"))
    )
    (net (code "158") (name "unconnected-(IC23-PC2(ADC2)-Pad25)") (class "Default")
      (node (ref "IC23") (pin "25") (pinfunction "PC2(ADC2)_25") (pintype "bidirectional"))
    )
    (net (code "159") (name "unconnected-(IC23-PC3(ADC3)-Pad26)") (class "Default")
      (node (ref "IC23") (pin "26") (pinfunction "PC3(ADC3)_26") (pintype "bidirectional"))
    )
    (net (code "160") (name "unconnected-(IC23-PC4(ADC4{slash}SDA)-Pad27)") (class "Default")
      (node (ref "IC23") (pin "27") (pinfunction "PC4(ADC4/SDA)_27") (pintype "bidirectional"))
    )
    (net (code "161") (name "unconnected-(IC23-PC5(ADC5{slash}SCL)-Pad28)") (class "Default")
      (node (ref "IC23") (pin "28") (pinfunction "PC5(ADC5/SCL)_28") (pintype "bidirectional"))
    )
    (net (code "162") (name "unconnected-(IC23-PD0(RXD)-Pad30)") (class "Default")
      (node (ref "IC23") (pin "30") (pinfunction "PD0(RXD)_30") (pintype "bidirectional"))
    )
    (net (code "163") (name "unconnected-(IC23-PD1(TXD)-Pad31)") (class "Default")
      (node (ref "IC23") (pin "31") (pinfunction "PD1(TXD)_31") (pintype "bidirectional"))
    )
    (net (code "164") (name "unconnected-(IC23-PD2(INT0)-Pad32)") (class "Default")
      (node (ref "IC23") (pin "32") (pinfunction "PD2(INT0)_32") (pintype "bidirectional"))
    )
    (net (code "165") (name "unconnected-(IC23-PD3(INT1)-Pad1)") (class "Default")
      (node (ref "IC23") (pin "1") (pinfunction "PD3(INT1)_1") (pintype "bidirectional"))
    )
    (net (code "166") (name "unconnected-(IC23-PD4(XCK{slash}T0)-Pad2)") (class "Default")
      (node (ref "IC23") (pin "2") (pinfunction "PD4(XCK/T0)_2") (pintype "bidirectional"))
    )
    (net (code "167") (name "unconnected-(IC23-PD5(T1)-Pad9)") (class "Default")
      (node (ref "IC23") (pin "9") (pinfunction "PD5(T1)_9") (pintype "bidirectional"))
    )
    (net (code "168") (name "unconnected-(IC23-PD6(AIN0)-Pad10)") (class "Default")
      (node (ref "IC23") (pin "10") (pinfunction "PD6(AIN0)_10") (pintype "bidirectional"))
    )
    (net (code "169") (name "unconnected-(IC23-PD7(AIN1)-Pad11)") (class "Default")
      (node (ref "IC23") (pin "11") (pinfunction "PD7(AIN1)_11") (pintype "bidirectional"))
    )
    (net (code "170") (name "unconnected-(J1-Pad2)") (class "Default")
      (node (ref "J1") (pin "2") (pinfunction "2_2") (pintype "passive"))
    )
    (net (code "171") (name "unconnected-(R25-Pad1)") (class "Default")
      (node (ref "R25") (pin "1") (pinfunction "1_1") (pintype "passive"))
    )
    (net (code "172") (name "unconnected-(R25-Pad2)") (class "Default")
      (node (ref "R25") (pin "2") (pinfunction "2_2") (pintype "passive"))
    )
  )
)
